# 05_08.net
KiCad netlist of a schematic drawn in EAGLE
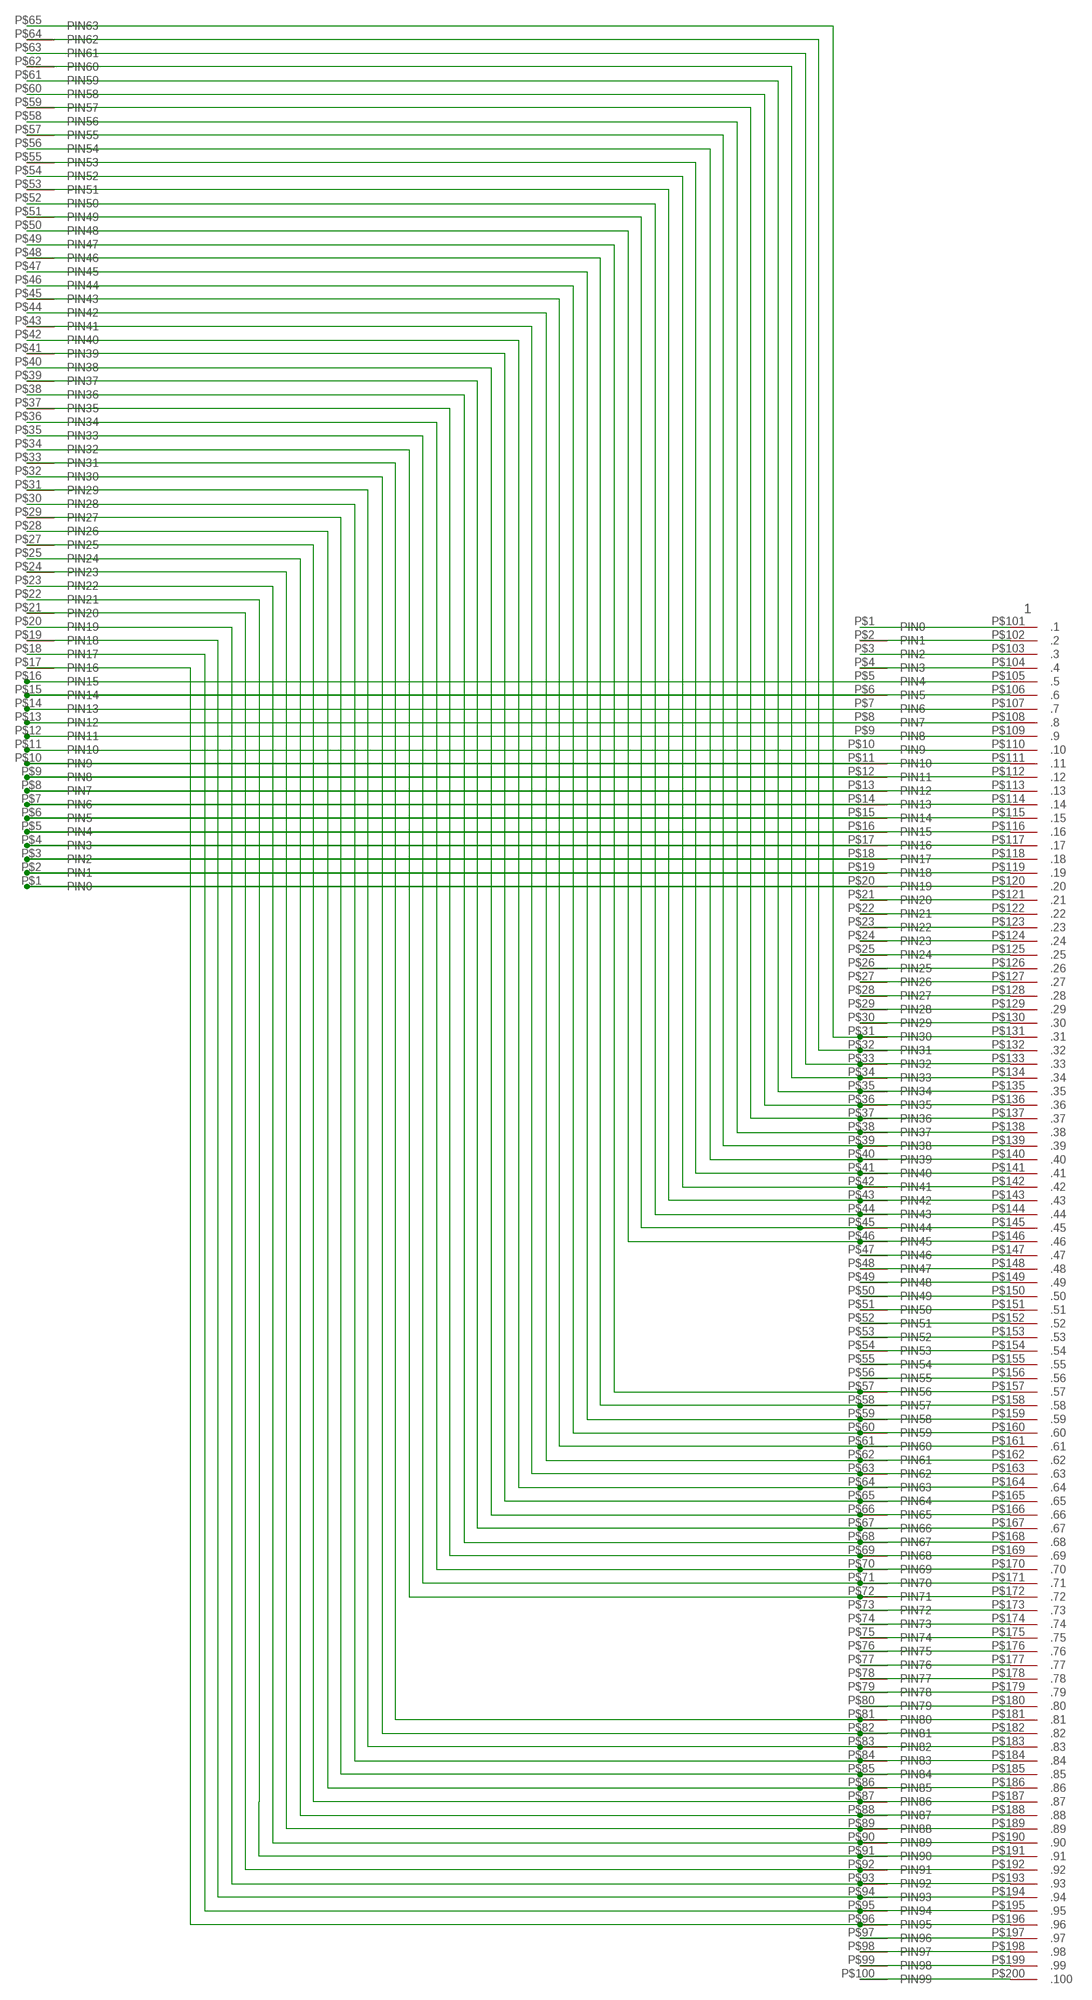
[diagram p0: schematic, sheet 1]

(export (version "E")
  (design (tool "Eeschema 10.0.6"))
  (components
    (comp (ref "U$1")
      (value "TQFP_100_PIN_1")
      (footprint "eagle-import:TQFP_100PIN_PCB_1")
      (libsource (lib "eagle-import") (part "TQFP_100_PIN_1"))
    )
    (comp (ref "U$2")
      (value "TQFP_100_PIN_2")
      (footprint "eagle-import:TQFP_100PIN_PCB_2")
      (libsource (lib "eagle-import") (part "TQFP_100_PIN_2"))
    )
    (comp (ref "U$3")
      (value "TQFP_64_PIN")
      (footprint "eagle-import:TQFP_100PIN_PCB_08")
      (libsource (lib "eagle-import") (part "TQFP_64_PIN"))
    )
  )
  (nets
    (net (code "1") (name "/1") (class "Default")
      (node (ref "U$1") (pin "P$1") (pinfunction "PIN0_P$1") (pintype "bidirectional"))
      (node (ref "U$2") (pin "P$101") (pinfunction ".1_P$101") (pintype "bidirectional"))
    )
    (net (code "2") (name "Net-(U$1-PIN1)") (class "Default")
      (node (ref "U$1") (pin "P$2") (pinfunction "PIN1_P$2") (pintype "bidirectional"))
      (node (ref "U$2") (pin "P$102") (pinfunction ".2_P$102") (pintype "bidirectional"))
    )
    (net (code "3") (name "Net-(U$1-PIN2)") (class "Default")
      (node (ref "U$1") (pin "P$3") (pinfunction "PIN2_P$3") (pintype "bidirectional"))
      (node (ref "U$2") (pin "P$103") (pinfunction ".3_P$103") (pintype "bidirectional"))
    )
    (net (code "4") (name "Net-(U$1-PIN3)") (class "Default")
      (node (ref "U$1") (pin "P$4") (pinfunction "PIN3_P$4") (pintype "bidirectional"))
      (node (ref "U$2") (pin "P$104") (pinfunction ".4_P$104") (pintype "bidirectional"))
    )
    (net (code "5") (name "Net-(U$1-PIN4)") (class "Default")
      (node (ref "U$1") (pin "P$5") (pinfunction "PIN4_P$5") (pintype "bidirectional"))
      (node (ref "U$2") (pin "P$105") (pinfunction ".5_P$105") (pintype "bidirectional"))
      (node (ref "U$3") (pin "P$16") (pinfunction "PIN15_P$16") (pintype "bidirectional"))
    )
    (net (code "6") (name "Net-(U$1-PIN5)") (class "Default")
      (node (ref "U$1") (pin "P$6") (pinfunction "PIN5_P$6") (pintype "bidirectional"))
      (node (ref "U$2") (pin "P$106") (pinfunction ".6_P$106") (pintype "bidirectional"))
      (node (ref "U$3") (pin "P$15") (pinfunction "PIN14_P$15") (pintype "bidirectional"))
    )
    (net (code "7") (name "Net-(U$1-PIN6)") (class "Default")
      (node (ref "U$1") (pin "P$7") (pinfunction "PIN6_P$7") (pintype "bidirectional"))
      (node (ref "U$2") (pin "P$107") (pinfunction ".7_P$107") (pintype "bidirectional"))
      (node (ref "U$3") (pin "P$14") (pinfunction "PIN13_P$14") (pintype "bidirectional"))
    )
    (net (code "8") (name "Net-(U$1-PIN7)") (class "Default")
      (node (ref "U$1") (pin "P$8") (pinfunction "PIN7_P$8") (pintype "bidirectional"))
      (node (ref "U$2") (pin "P$108") (pinfunction ".8_P$108") (pintype "bidirectional"))
      (node (ref "U$3") (pin "P$13") (pinfunction "PIN12_P$13") (pintype "bidirectional"))
    )
    (net (code "9") (name "Net-(U$1-PIN8)") (class "Default")
      (node (ref "U$1") (pin "P$9") (pinfunction "PIN8_P$9") (pintype "bidirectional"))
      (node (ref "U$2") (pin "P$109") (pinfunction ".9_P$109") (pintype "bidirectional"))
      (node (ref "U$3") (pin "P$12") (pinfunction "PIN11_P$12") (pintype "bidirectional"))
    )
    (net (code "10") (name "Net-(U$1-PIN9)") (class "Default")
      (node (ref "U$1") (pin "P$10") (pinfunction "PIN9_P$10") (pintype "bidirectional"))
      (node (ref "U$2") (pin "P$110") (pinfunction ".10_P$110") (pintype "bidirectional"))
      (node (ref "U$3") (pin "P$11") (pinfunction "PIN10_P$11") (pintype "bidirectional"))
    )
    (net (code "11") (name "Net-(U$1-PIN10)") (class "Default")
      (node (ref "U$1") (pin "P$11") (pinfunction "PIN10_P$11") (pintype "bidirectional"))
      (node (ref "U$2") (pin "P$111") (pinfunction ".11_P$111") (pintype "bidirectional"))
      (node (ref "U$3") (pin "P$10") (pinfunction "PIN9_P$10") (pintype "bidirectional"))
    )
    (net (code "12") (name "Net-(U$1-PIN11)") (class "Default")
      (node (ref "U$1") (pin "P$12") (pinfunction "PIN11_P$12") (pintype "bidirectional"))
      (node (ref "U$2") (pin "P$112") (pinfunction ".12_P$112") (pintype "bidirectional"))
      (node (ref "U$3") (pin "P$9") (pinfunction "PIN8_P$9") (pintype "bidirectional"))
    )
    (net (code "13") (name "Net-(U$1-PIN12)") (class "Default")
      (node (ref "U$1") (pin "P$13") (pinfunction "PIN12_P$13") (pintype "bidirectional"))
      (node (ref "U$2") (pin "P$113") (pinfunction ".13_P$113") (pintype "bidirectional"))
      (node (ref "U$3") (pin "P$8") (pinfunction "PIN7_P$8") (pintype "bidirectional"))
    )
    (net (code "14") (name "Net-(U$1-PIN13)") (class "Default")
      (node (ref "U$1") (pin "P$14") (pinfunction "PIN13_P$14") (pintype "bidirectional"))
      (node (ref "U$2") (pin "P$114") (pinfunction ".14_P$114") (pintype "bidirectional"))
      (node (ref "U$3") (pin "P$7") (pinfunction "PIN6_P$7") (pintype "bidirectional"))
    )
    (net (code "15") (name "Net-(U$1-PIN14)") (class "Default")
      (node (ref "U$1") (pin "P$15") (pinfunction "PIN14_P$15") (pintype "bidirectional"))
      (node (ref "U$2") (pin "P$115") (pinfunction ".15_P$115") (pintype "bidirectional"))
      (node (ref "U$3") (pin "P$6") (pinfunction "PIN5_P$6") (pintype "bidirectional"))
    )
    (net (code "16") (name "Net-(U$1-PIN15)") (class "Default")
      (node (ref "U$1") (pin "P$16") (pinfunction "PIN15_P$16") (pintype "bidirectional"))
      (node (ref "U$2") (pin "P$116") (pinfunction ".16_P$116") (pintype "bidirectional"))
      (node (ref "U$3") (pin "P$5") (pinfunction "PIN4_P$5") (pintype "bidirectional"))
    )
    (net (code "17") (name "Net-(U$1-PIN16)") (class "Default")
      (node (ref "U$1") (pin "P$17") (pinfunction "PIN16_P$17") (pintype "bidirectional"))
      (node (ref "U$2") (pin "P$117") (pinfunction ".17_P$117") (pintype "bidirectional"))
      (node (ref "U$3") (pin "P$4") (pinfunction "PIN3_P$4") (pintype "bidirectional"))
    )
    (net (code "18") (name "Net-(U$1-PIN17)") (class "Default")
      (node (ref "U$1") (pin "P$18") (pinfunction "PIN17_P$18") (pintype "bidirectional"))
      (node (ref "U$2") (pin "P$118") (pinfunction ".18_P$118") (pintype "bidirectional"))
      (node (ref "U$3") (pin "P$3") (pinfunction "PIN2_P$3") (pintype "bidirectional"))
    )
    (net (code "19") (name "Net-(U$1-PIN18)") (class "Default")
      (node (ref "U$1") (pin "P$19") (pinfunction "PIN18_P$19") (pintype "bidirectional"))
      (node (ref "U$2") (pin "P$119") (pinfunction ".19_P$119") (pintype "bidirectional"))
      (node (ref "U$3") (pin "P$2") (pinfunction "PIN1_P$2") (pintype "bidirectional"))
    )
    (net (code "20") (name "Net-(U$1-PIN19)") (class "Default")
      (node (ref "U$1") (pin "P$20") (pinfunction "PIN19_P$20") (pintype "bidirectional"))
      (node (ref "U$2") (pin "P$120") (pinfunction ".20_P$120") (pintype "bidirectional"))
      (node (ref "U$3") (pin "P$1") (pinfunction "PIN0_P$1") (pintype "bidirectional"))
    )
    (net (code "21") (name "Net-(U$1-PIN20)") (class "Default")
      (node (ref "U$1") (pin "P$21") (pinfunction "PIN20_P$21") (pintype "bidirectional"))
      (node (ref "U$2") (pin "P$121") (pinfunction ".21_P$121") (pintype "bidirectional"))
    )
    (net (code "22") (name "Net-(U$1-PIN21)") (class "Default")
      (node (ref "U$1") (pin "P$22") (pinfunction "PIN21_P$22") (pintype "bidirectional"))
      (node (ref "U$2") (pin "P$122") (pinfunction ".22_P$122") (pintype "bidirectional"))
    )
    (net (code "23") (name "Net-(U$1-PIN22)") (class "Default")
      (node (ref "U$1") (pin "P$23") (pinfunction "PIN22_P$23") (pintype "bidirectional"))
      (node (ref "U$2") (pin "P$123") (pinfunction ".23_P$123") (pintype "bidirectional"))
    )
    (net (code "24") (name "Net-(U$1-PIN23)") (class "Default")
      (node (ref "U$1") (pin "P$24") (pinfunction "PIN23_P$24") (pintype "bidirectional"))
      (node (ref "U$2") (pin "P$124") (pinfunction ".24_P$124") (pintype "bidirectional"))
    )
    (net (code "25") (name "Net-(U$1-PIN24)") (class "Default")
      (node (ref "U$1") (pin "P$25") (pinfunction "PIN24_P$25") (pintype "bidirectional"))
      (node (ref "U$2") (pin "P$125") (pinfunction ".25_P$125") (pintype "bidirectional"))
    )
    (net (code "26") (name "Net-(U$1-PIN25)") (class "Default")
      (node (ref "U$1") (pin "P$26") (pinfunction "PIN25_P$26") (pintype "bidirectional"))
      (node (ref "U$2") (pin "P$126") (pinfunction ".26_P$126") (pintype "bidirectional"))
    )
    (net (code "27") (name "Net-(U$1-PIN26)") (class "Default")
      (node (ref "U$1") (pin "P$27") (pinfunction "PIN26_P$27") (pintype "bidirectional"))
      (node (ref "U$2") (pin "P$127") (pinfunction ".27_P$127") (pintype "bidirectional"))
    )
    (net (code "28") (name "Net-(U$1-PIN27)") (class "Default")
      (node (ref "U$1") (pin "P$28") (pinfunction "PIN27_P$28") (pintype "bidirectional"))
      (node (ref "U$2") (pin "P$128") (pinfunction ".28_P$128") (pintype "bidirectional"))
    )
    (net (code "29") (name "Net-(U$1-PIN28)") (class "Default")
      (node (ref "U$1") (pin "P$29") (pinfunction "PIN28_P$29") (pintype "bidirectional"))
      (node (ref "U$2") (pin "P$129") (pinfunction ".29_P$129") (pintype "bidirectional"))
    )
    (net (code "30") (name "Net-(U$1-PIN29)") (class "Default")
      (node (ref "U$1") (pin "P$30") (pinfunction "PIN29_P$30") (pintype "bidirectional"))
      (node (ref "U$2") (pin "P$130") (pinfunction ".30_P$130") (pintype "bidirectional"))
    )
    (net (code "31") (name "Net-(U$1-PIN30)") (class "Default")
      (node (ref "U$1") (pin "P$31") (pinfunction "PIN30_P$31") (pintype "bidirectional"))
      (node (ref "U$2") (pin "P$131") (pinfunction ".31_P$131") (pintype "bidirectional"))
      (node (ref "U$3") (pin "P$65") (pinfunction "PIN63_P$65") (pintype "bidirectional"))
    )
    (net (code "32") (name "Net-(U$1-PIN31)") (class "Default")
      (node (ref "U$1") (pin "P$32") (pinfunction "PIN31_P$32") (pintype "bidirectional"))
      (node (ref "U$2") (pin "P$132") (pinfunction ".32_P$132") (pintype "bidirectional"))
      (node (ref "U$3") (pin "P$64") (pinfunction "PIN62_P$64") (pintype "bidirectional"))
    )
    (net (code "33") (name "Net-(U$1-PIN32)") (class "Default")
      (node (ref "U$1") (pin "P$33") (pinfunction "PIN32_P$33") (pintype "bidirectional"))
      (node (ref "U$2") (pin "P$133") (pinfunction ".33_P$133") (pintype "bidirectional"))
      (node (ref "U$3") (pin "P$63") (pinfunction "PIN61_P$63") (pintype "bidirectional"))
    )
    (net (code "34") (name "Net-(U$1-PIN33)") (class "Default")
      (node (ref "U$1") (pin "P$34") (pinfunction "PIN33_P$34") (pintype "bidirectional"))
      (node (ref "U$2") (pin "P$134") (pinfunction ".34_P$134") (pintype "bidirectional"))
      (node (ref "U$3") (pin "P$62") (pinfunction "PIN60_P$62") (pintype "bidirectional"))
    )
    (net (code "35") (name "Net-(U$1-PIN34)") (class "Default")
      (node (ref "U$1") (pin "P$35") (pinfunction "PIN34_P$35") (pintype "bidirectional"))
      (node (ref "U$2") (pin "P$135") (pinfunction ".35_P$135") (pintype "bidirectional"))
      (node (ref "U$3") (pin "P$61") (pinfunction "PIN59_P$61") (pintype "bidirectional"))
    )
    (net (code "36") (name "Net-(U$1-PIN35)") (class "Default")
      (node (ref "U$1") (pin "P$36") (pinfunction "PIN35_P$36") (pintype "bidirectional"))
      (node (ref "U$2") (pin "P$136") (pinfunction ".36_P$136") (pintype "bidirectional"))
      (node (ref "U$3") (pin "P$60") (pinfunction "PIN58_P$60") (pintype "bidirectional"))
    )
    (net (code "37") (name "Net-(U$1-PIN36)") (class "Default")
      (node (ref "U$1") (pin "P$37") (pinfunction "PIN36_P$37") (pintype "bidirectional"))
      (node (ref "U$2") (pin "P$137") (pinfunction ".37_P$137") (pintype "bidirectional"))
      (node (ref "U$3") (pin "P$59") (pinfunction "PIN57_P$59") (pintype "bidirectional"))
    )
    (net (code "38") (name "Net-(U$1-PIN37)") (class "Default")
      (node (ref "U$1") (pin "P$38") (pinfunction "PIN37_P$38") (pintype "bidirectional"))
      (node (ref "U$2") (pin "P$138") (pinfunction ".38_P$138") (pintype "bidirectional"))
      (node (ref "U$3") (pin "P$58") (pinfunction "PIN56_P$58") (pintype "bidirectional"))
    )
    (net (code "39") (name "Net-(U$1-PIN38)") (class "Default")
      (node (ref "U$1") (pin "P$39") (pinfunction "PIN38_P$39") (pintype "bidirectional"))
      (node (ref "U$2") (pin "P$139") (pinfunction ".39_P$139") (pintype "bidirectional"))
      (node (ref "U$3") (pin "P$57") (pinfunction "PIN55_P$57") (pintype "bidirectional"))
    )
    (net (code "40") (name "Net-(U$1-PIN39)") (class "Default")
      (node (ref "U$1") (pin "P$40") (pinfunction "PIN39_P$40") (pintype "bidirectional"))
      (node (ref "U$2") (pin "P$140") (pinfunction ".40_P$140") (pintype "bidirectional"))
      (node (ref "U$3") (pin "P$56") (pinfunction "PIN54_P$56") (pintype "bidirectional"))
    )
    (net (code "41") (name "Net-(U$1-PIN40)") (class "Default")
      (node (ref "U$1") (pin "P$41") (pinfunction "PIN40_P$41") (pintype "bidirectional"))
      (node (ref "U$2") (pin "P$141") (pinfunction ".41_P$141") (pintype "bidirectional"))
      (node (ref "U$3") (pin "P$55") (pinfunction "PIN53_P$55") (pintype "bidirectional"))
    )
    (net (code "42") (name "Net-(U$1-PIN41)") (class "Default")
      (node (ref "U$1") (pin "P$42") (pinfunction "PIN41_P$42") (pintype "bidirectional"))
      (node (ref "U$2") (pin "P$142") (pinfunction ".42_P$142") (pintype "bidirectional"))
      (node (ref "U$3") (pin "P$54") (pinfunction "PIN52_P$54") (pintype "bidirectional"))
    )
    (net (code "43") (name "Net-(U$1-PIN42)") (class "Default")
      (node (ref "U$1") (pin "P$43") (pinfunction "PIN42_P$43") (pintype "bidirectional"))
      (node (ref "U$2") (pin "P$143") (pinfunction ".43_P$143") (pintype "bidirectional"))
      (node (ref "U$3") (pin "P$53") (pinfunction "PIN51_P$53") (pintype "bidirectional"))
    )
    (net (code "44") (name "Net-(U$1-PIN43)") (class "Default")
      (node (ref "U$1") (pin "P$44") (pinfunction "PIN43_P$44") (pintype "bidirectional"))
      (node (ref "U$2") (pin "P$144") (pinfunction ".44_P$144") (pintype "bidirectional"))
      (node (ref "U$3") (pin "P$52") (pinfunction "PIN50_P$52") (pintype "bidirectional"))
    )
    (net (code "45") (name "Net-(U$1-PIN44)") (class "Default")
      (node (ref "U$1") (pin "P$45") (pinfunction "PIN44_P$45") (pintype "bidirectional"))
      (node (ref "U$2") (pin "P$145") (pinfunction ".45_P$145") (pintype "bidirectional"))
      (node (ref "U$3") (pin "P$51") (pinfunction "PIN49_P$51") (pintype "bidirectional"))
    )
    (net (code "46") (name "Net-(U$1-PIN45)") (class "Default")
      (node (ref "U$1") (pin "P$46") (pinfunction "PIN45_P$46") (pintype "bidirectional"))
      (node (ref "U$2") (pin "P$146") (pinfunction ".46_P$146") (pintype "bidirectional"))
      (node (ref "U$3") (pin "P$50") (pinfunction "PIN48_P$50") (pintype "bidirectional"))
    )
    (net (code "47") (name "Net-(U$1-PIN46)") (class "Default")
      (node (ref "U$1") (pin "P$47") (pinfunction "PIN46_P$47") (pintype "bidirectional"))
      (node (ref "U$2") (pin "P$147") (pinfunction ".47_P$147") (pintype "bidirectional"))
    )
    (net (code "48") (name "Net-(U$1-PIN47)") (class "Default")
      (node (ref "U$1") (pin "P$48") (pinfunction "PIN47_P$48") (pintype "bidirectional"))
      (node (ref "U$2") (pin "P$148") (pinfunction ".48_P$148") (pintype "bidirectional"))
    )
    (net (code "49") (name "Net-(U$1-PIN48)") (class "Default")
      (node (ref "U$1") (pin "P$49") (pinfunction "PIN48_P$49") (pintype "bidirectional"))
      (node (ref "U$2") (pin "P$149") (pinfunction ".49_P$149") (pintype "bidirectional"))
    )
    (net (code "50") (name "Net-(U$1-PIN49)") (class "Default")
      (node (ref "U$1") (pin "P$50") (pinfunction "PIN49_P$50") (pintype "bidirectional"))
      (node (ref "U$2") (pin "P$150") (pinfunction ".50_P$150") (pintype "bidirectional"))
    )
    (net (code "51") (name "Net-(U$1-PIN50)") (class "Default")
      (node (ref "U$1") (pin "P$51") (pinfunction "PIN50_P$51") (pintype "bidirectional"))
      (node (ref "U$2") (pin "P$151") (pinfunction ".51_P$151") (pintype "bidirectional"))
    )
    (net (code "52") (name "Net-(U$1-PIN51)") (class "Default")
      (node (ref "U$1") (pin "P$52") (pinfunction "PIN51_P$52") (pintype "bidirectional"))
      (node (ref "U$2") (pin "P$152") (pinfunction ".52_P$152") (pintype "bidirectional"))
    )
    (net (code "53") (name "Net-(U$1-PIN52)") (class "Default")
      (node (ref "U$1") (pin "P$53") (pinfunction "PIN52_P$53") (pintype "bidirectional"))
      (node (ref "U$2") (pin "P$153") (pinfunction ".53_P$153") (pintype "bidirectional"))
    )
    (net (code "54") (name "Net-(U$1-PIN53)") (class "Default")
      (node (ref "U$1") (pin "P$54") (pinfunction "PIN53_P$54") (pintype "bidirectional"))
      (node (ref "U$2") (pin "P$154") (pinfunction ".54_P$154") (pintype "bidirectional"))
    )
    (net (code "55") (name "Net-(U$1-PIN54)") (class "Default")
      (node (ref "U$1") (pin "P$55") (pinfunction "PIN54_P$55") (pintype "bidirectional"))
      (node (ref "U$2") (pin "P$155") (pinfunction ".55_P$155") (pintype "bidirectional"))
    )
    (net (code "56") (name "Net-(U$1-PIN55)") (class "Default")
      (node (ref "U$1") (pin "P$56") (pinfunction "PIN55_P$56") (pintype "bidirectional"))
      (node (ref "U$2") (pin "P$156") (pinfunction ".56_P$156") (pintype "bidirectional"))
    )
    (net (code "57") (name "Net-(U$1-PIN56)") (class "Default")
      (node (ref "U$1") (pin "P$57") (pinfunction "PIN56_P$57") (pintype "bidirectional"))
      (node (ref "U$2") (pin "P$157") (pinfunction ".57_P$157") (pintype "bidirectional"))
      (node (ref "U$3") (pin "P$49") (pinfunction "PIN47_P$49") (pintype "bidirectional"))
    )
    (net (code "58") (name "Net-(U$1-PIN57)") (class "Default")
      (node (ref "U$1") (pin "P$58") (pinfunction "PIN57_P$58") (pintype "bidirectional"))
      (node (ref "U$2") (pin "P$158") (pinfunction ".58_P$158") (pintype "bidirectional"))
      (node (ref "U$3") (pin "P$48") (pinfunction "PIN46_P$48") (pintype "bidirectional"))
    )
    (net (code "59") (name "Net-(U$1-PIN58)") (class "Default")
      (node (ref "U$1") (pin "P$59") (pinfunction "PIN58_P$59") (pintype "bidirectional"))
      (node (ref "U$2") (pin "P$159") (pinfunction ".59_P$159") (pintype "bidirectional"))
      (node (ref "U$3") (pin "P$47") (pinfunction "PIN45_P$47") (pintype "bidirectional"))
    )
    (net (code "60") (name "Net-(U$1-PIN59)") (class "Default")
      (node (ref "U$1") (pin "P$60") (pinfunction "PIN59_P$60") (pintype "bidirectional"))
      (node (ref "U$2") (pin "P$160") (pinfunction ".60_P$160") (pintype "bidirectional"))
      (node (ref "U$3") (pin "P$46") (pinfunction "PIN44_P$46") (pintype "bidirectional"))
    )
    (net (code "61") (name "Net-(U$1-PIN60)") (class "Default")
      (node (ref "U$1") (pin "P$61") (pinfunction "PIN60_P$61") (pintype "bidirectional"))
      (node (ref "U$2") (pin "P$161") (pinfunction ".61_P$161") (pintype "bidirectional"))
      (node (ref "U$3") (pin "P$45") (pinfunction "PIN43_P$45") (pintype "bidirectional"))
    )
    (net (code "62") (name "Net-(U$1-PIN61)") (class "Default")
      (node (ref "U$1") (pin "P$62") (pinfunction "PIN61_P$62") (pintype "bidirectional"))
      (node (ref "U$2") (pin "P$162") (pinfunction ".62_P$162") (pintype "bidirectional"))
      (node (ref "U$3") (pin "P$44") (pinfunction "PIN42_P$44") (pintype "bidirectional"))
    )
    (net (code "63") (name "Net-(U$1-PIN62)") (class "Default")
      (node (ref "U$1") (pin "P$63") (pinfunction "PIN62_P$63") (pintype "bidirectional"))
      (node (ref "U$2") (pin "P$163") (pinfunction ".63_P$163") (pintype "bidirectional"))
      (node (ref "U$3") (pin "P$43") (pinfunction "PIN41_P$43") (pintype "bidirectional"))
    )
    (net (code "64") (name "Net-(U$1-PIN63)") (class "Default")
      (node (ref "U$1") (pin "P$64") (pinfunction "PIN63_P$64") (pintype "bidirectional"))
      (node (ref "U$2") (pin "P$164") (pinfunction ".64_P$164") (pintype "bidirectional"))
      (node (ref "U$3") (pin "P$42") (pinfunction "PIN40_P$42") (pintype "bidirectional"))
    )
    (net (code "65") (name "Net-(U$1-PIN64)") (class "Default")
      (node (ref "U$1") (pin "P$65") (pinfunction "PIN64_P$65") (pintype "bidirectional"))
      (node (ref "U$2") (pin "P$165") (pinfunction ".65_P$165") (pintype "bidirectional"))
      (node (ref "U$3") (pin "P$41") (pinfunction "PIN39_P$41") (pintype "bidirectional"))
    )
    (net (code "66") (name "Net-(U$1-PIN65)") (class "Default")
      (node (ref "U$1") (pin "P$66") (pinfunction "PIN65_P$66") (pintype "bidirectional"))
      (node (ref "U$2") (pin "P$166") (pinfunction ".66_P$166") (pintype "bidirectional"))
      (node (ref "U$3") (pin "P$40") (pinfunction "PIN38_P$40") (pintype "bidirectional"))
    )
    (net (code "67") (name "Net-(U$1-PIN66)") (class "Default")
      (node (ref "U$1") (pin "P$67") (pinfunction "PIN66_P$67") (pintype "bidirectional"))
      (node (ref "U$2") (pin "P$167") (pinfunction ".67_P$167") (pintype "bidirectional"))
      (node (ref "U$3") (pin "P$39") (pinfunction "PIN37_P$39") (pintype "bidirectional"))
    )
    (net (code "68") (name "Net-(U$1-PIN67)") (class "Default")
      (node (ref "U$1") (pin "P$68") (pinfunction "PIN67_P$68") (pintype "bidirectional"))
      (node (ref "U$2") (pin "P$168") (pinfunction ".68_P$168") (pintype "bidirectional"))
      (node (ref "U$3") (pin "P$38") (pinfunction "PIN36_P$38") (pintype "bidirectional"))
    )
    (net (code "69") (name "Net-(U$1-PIN68)") (class "Default")
      (node (ref "U$1") (pin "P$69") (pinfunction "PIN68_P$69") (pintype "bidirectional"))
      (node (ref "U$2") (pin "P$169") (pinfunction ".69_P$169") (pintype "bidirectional"))
      (node (ref "U$3") (pin "P$37") (pinfunction "PIN35_P$37") (pintype "bidirectional"))
    )
    (net (code "70") (name "Net-(U$1-PIN69)") (class "Default")
      (node (ref "U$1") (pin "P$70") (pinfunction "PIN69_P$70") (pintype "bidirectional"))
      (node (ref "U$2") (pin "P$170") (pinfunction ".70_P$170") (pintype "bidirectional"))
      (node (ref "U$3") (pin "P$36") (pinfunction "PIN34_P$36") (pintype "bidirectional"))
    )
    (net (code "71") (name "Net-(U$1-PIN70)") (class "Default")
      (node (ref "U$1") (pin "P$71") (pinfunction "PIN70_P$71") (pintype "bidirectional"))
      (node (ref "U$2") (pin "P$171") (pinfunction ".71_P$171") (pintype "bidirectional"))
      (node (ref "U$3") (pin "P$35") (pinfunction "PIN33_P$35") (pintype "bidirectional"))
    )
    (net (code "72") (name "Net-(U$1-PIN71)") (class "Default")
      (node (ref "U$1") (pin "P$72") (pinfunction "PIN71_P$72") (pintype "bidirectional"))
      (node (ref "U$2") (pin "P$172") (pinfunction ".72_P$172") (pintype "bidirectional"))
      (node (ref "U$3") (pin "P$34") (pinfunction "PIN32_P$34") (pintype "bidirectional"))
    )
    (net (code "73") (name "Net-(U$1-PIN72)") (class "Default")
      (node (ref "U$1") (pin "P$73") (pinfunction "PIN72_P$73") (pintype "bidirectional"))
      (node (ref "U$2") (pin "P$173") (pinfunction ".73_P$173") (pintype "bidirectional"))
    )
    (net (code "74") (name "Net-(U$1-PIN73)") (class "Default")
      (node (ref "U$1") (pin "P$74") (pinfunction "PIN73_P$74") (pintype "bidirectional"))
      (node (ref "U$2") (pin "P$174") (pinfunction ".74_P$174") (pintype "bidirectional"))
    )
    (net (code "75") (name "Net-(U$1-PIN74)") (class "Default")
      (node (ref "U$1") (pin "P$75") (pinfunction "PIN74_P$75") (pintype "bidirectional"))
      (node (ref "U$2") (pin "P$175") (pinfunction ".75_P$175") (pintype "bidirectional"))
    )
    (net (code "76") (name "Net-(U$1-PIN75)") (class "Default")
      (node (ref "U$1") (pin "P$76") (pinfunction "PIN75_P$76") (pintype "bidirectional"))
      (node (ref "U$2") (pin "P$176") (pinfunction ".76_P$176") (pintype "bidirectional"))
    )
    (net (code "77") (name "Net-(U$1-PIN76)") (class "Default")
      (node (ref "U$1") (pin "P$77") (pinfunction "PIN76_P$77") (pintype "bidirectional"))
      (node (ref "U$2") (pin "P$177") (pinfunction ".77_P$177") (pintype "bidirectional"))
    )
    (net (code "78") (name "Net-(U$1-PIN77)") (class "Default")
      (node (ref "U$1") (pin "P$78") (pinfunction "PIN77_P$78") (pintype "bidirectional"))
      (node (ref "U$2") (pin "P$178") (pinfunction ".78_P$178") (pintype "bidirectional"))
    )
    (net (code "79") (name "Net-(U$1-PIN78)") (class "Default")
      (node (ref "U$1") (pin "P$79") (pinfunction "PIN78_P$79") (pintype "bidirectional"))
      (node (ref "U$2") (pin "P$179") (pinfunction ".79_P$179") (pintype "bidirectional"))
    )
    (net (code "80") (name "Net-(U$1-PIN79)") (class "Default")
      (node (ref "U$1") (pin "P$80") (pinfunction "PIN79_P$80") (pintype "bidirectional"))
      (node (ref "U$2") (pin "P$180") (pinfunction ".80_P$180") (pintype "bidirectional"))
    )
    (net (code "81") (name "Net-(U$1-PIN80)") (class "Default")
      (node (ref "U$1") (pin "P$81") (pinfunction "PIN80_P$81") (pintype "bidirectional"))
      (node (ref "U$2") (pin "P$181") (pinfunction ".81_P$181") (pintype "bidirectional"))
      (node (ref "U$3") (pin "P$33") (pinfunction "PIN31_P$33") (pintype "bidirectional"))
    )
    (net (code "82") (name "Net-(U$1-PIN81)") (class "Default")
      (node (ref "U$1") (pin "P$82") (pinfunction "PIN81_P$82") (pintype "bidirectional"))
      (node (ref "U$2") (pin "P$182") (pinfunction ".82_P$182") (pintype "bidirectional"))
      (node (ref "U$3") (pin "P$32") (pinfunction "PIN30_P$32") (pintype "bidirectional"))
    )
    (net (code "83") (name "Net-(U$1-PIN82)") (class "Default")
      (node (ref "U$1") (pin "P$83") (pinfunction "PIN82_P$83") (pintype "bidirectional"))
      (node (ref "U$2") (pin "P$183") (pinfunction ".83_P$183") (pintype "bidirectional"))
      (node (ref "U$3") (pin "P$31") (pinfunction "PIN29_P$31") (pintype "bidirectional"))
    )
    (net (code "84") (name "Net-(U$1-PIN83)") (class "Default")
      (node (ref "U$1") (pin "P$84") (pinfunction "PIN83_P$84") (pintype "bidirectional"))
      (node (ref "U$2") (pin "P$184") (pinfunction ".84_P$184") (pintype "bidirectional"))
      (node (ref "U$3") (pin "P$30") (pinfunction "PIN28_P$30") (pintype "bidirectional"))
    )
    (net (code "85") (name "Net-(U$1-PIN84)") (class "Default")
      (node (ref "U$1") (pin "P$85") (pinfunction "PIN84_P$85") (pintype "bidirectional"))
      (node (ref "U$2") (pin "P$185") (pinfunction ".85_P$185") (pintype "bidirectional"))
      (node (ref "U$3") (pin "P$29") (pinfunction "PIN27_P$29") (pintype "bidirectional"))
    )
    (net (code "86") (name "Net-(U$1-PIN85)") (class "Default")
      (node (ref "U$1") (pin "P$86") (pinfunction "PIN85_P$86") (pintype "bidirectional"))
      (node (ref "U$2") (pin "P$186") (pinfunction ".86_P$186") (pintype "bidirectional"))
      (node (ref "U$3") (pin "P$28") (pinfunction "PIN26_P$28") (pintype "bidirectional"))
    )
    (net (code "87") (name "Net-(U$1-PIN86)") (class "Default")
      (node (ref "U$1") (pin "P$87") (pinfunction "PIN86_P$87") (pintype "bidirectional"))
      (node (ref "U$2") (pin "P$187") (pinfunction ".87_P$187") (pintype "bidirectional"))
      (node (ref "U$3") (pin "P$27") (pinfunction "PIN25_P$27") (pintype "bidirectional"))
    )
    (net (code "88") (name "Net-(U$1-PIN87)") (class "Default")
      (node (ref "U$1") (pin "P$88") (pinfunction "PIN87_P$88") (pintype "bidirectional"))
      (node (ref "U$2") (pin "P$188") (pinfunction ".88_P$188") (pintype "bidirectional"))
      (node (ref "U$3") (pin "P$25") (pinfunction "PIN24_P$25") (pintype "bidirectional"))
    )
    (net (code "89") (name "Net-(U$1-PIN88)") (class "Default")
      (node (ref "U$1") (pin "P$89") (pinfunction "PIN88_P$89") (pintype "bidirectional"))
      (node (ref "U$2") (pin "P$189") (pinfunction ".89_P$189") (pintype "bidirectional"))
      (node (ref "U$3") (pin "P$24") (pinfunction "PIN23_P$24") (pintype "bidirectional"))
    )
    (net (code "90") (name "Net-(U$1-PIN89)") (class "Default")
      (node (ref "U$1") (pin "P$90") (pinfunction "PIN89_P$90") (pintype "bidirectional"))
      (node (ref "U$2") (pin "P$190") (pinfunction ".90_P$190") (pintype "bidirectional"))
      (node (ref "U$3") (pin "P$23") (pinfunction "PIN22_P$23") (pintype "bidirectional"))
    )
    (net (code "91") (name "Net-(U$1-PIN90)") (class "Default")
      (node (ref "U$1") (pin "P$91") (pinfunction "PIN90_P$91") (pintype "bidirectional"))
      (node (ref "U$2") (pin "P$191") (pinfunction ".91_P$191") (pintype "bidirectional"))
      (node (ref "U$3") (pin "P$22") (pinfunction "PIN21_P$22") (pintype "bidirectional"))
    )
    (net (code "92") (name "Net-(U$1-PIN91)") (class "Default")
      (node (ref "U$1") (pin "P$92") (pinfunction "PIN91_P$92") (pintype "bidirectional"))
      (node (ref "U$2") (pin "P$192") (pinfunction ".92_P$192") (pintype "bidirectional"))
      (node (ref "U$3") (pin "P$21") (pinfunction "PIN20_P$21") (pintype "bidirectional"))
    )
    (net (code "93") (name "Net-(U$1-PIN92)") (class "Default")
      (node (ref "U$1") (pin "P$93") (pinfunction "PIN92_P$93") (pintype "bidirectional"))
      (node (ref "U$2") (pin "P$193") (pinfunction ".93_P$193") (pintype "bidirectional"))
      (node (ref "U$3") (pin "P$20") (pinfunction "PIN19_P$20") (pintype "bidirectional"))
    )
    (net (code "94") (name "Net-(U$1-PIN93)") (class "Default")
      (node (ref "U$1") (pin "P$94") (pinfunction "PIN93_P$94") (pintype "bidirectional"))
      (node (ref "U$2") (pin "P$194") (pinfunction ".94_P$194") (pintype "bidirectional"))
      (node (ref "U$3") (pin "P$19") (pinfunction "PIN18_P$19") (pintype "bidirectional"))
    )
    (net (code "95") (name "Net-(U$1-PIN94)") (class "Default")
      (node (ref "U$1") (pin "P$95") (pinfunction "PIN94_P$95") (pintype "bidirectional"))
      (node (ref "U$2") (pin "P$195") (pinfunction ".95_P$195") (pintype "bidirectional"))
      (node (ref "U$3") (pin "P$18") (pinfunction "PIN17_P$18") (pintype "bidirectional"))
    )
    (net (code "96") (name "Net-(U$1-PIN95)") (class "Default")
      (node (ref "U$1") (pin "P$96") (pinfunction "PIN95_P$96") (pintype "bidirectional"))
      (node (ref "U$2") (pin "P$196") (pinfunction ".96_P$196") (pintype "bidirectional"))
      (node (ref "U$3") (pin "P$17") (pinfunction "PIN16_P$17") (pintype "bidirectional"))
    )
    (net (code "97") (name "Net-(U$1-PIN96)") (class "Default")
      (node (ref "U$1") (pin "P$97") (pinfunction "PIN96_P$97") (pintype "bidirectional"))
      (node (ref "U$2") (pin "P$197") (pinfunction ".97_P$197") (pintype "bidirectional"))
    )
    (net (code "98") (name "Net-(U$1-PIN97)") (class "Default")
      (node (ref "U$1") (pin "P$98") (pinfunction "PIN97_P$98") (pintype "bidirectional"))
      (node (ref "U$2") (pin "P$198") (pinfunction ".98_P$198") (pintype "bidirectional"))
    )
    (net (code "99") (name "Net-(U$1-PIN98)") (class "Default")
      (node (ref "U$1") (pin "P$99") (pinfunction "PIN98_P$99") (pintype "bidirectional"))
      (node (ref "U$2") (pin "P$199") (pinfunction ".99_P$199") (pintype "bidirectional"))
    )
    (net (code "100") (name "Net-(U$1-PIN99)") (class "Default")
      (node (ref "U$1") (pin "P$100") (pinfunction "PIN99_P$100") (pintype "bidirectional"))
      (node (ref "U$2") (pin "P$200") (pinfunction ".100_P$200") (pintype "bidirectional"))
    )
  )
)
